# PX4IOv1_3.net
KiCad netlist of a schematic drawn in EAGLE
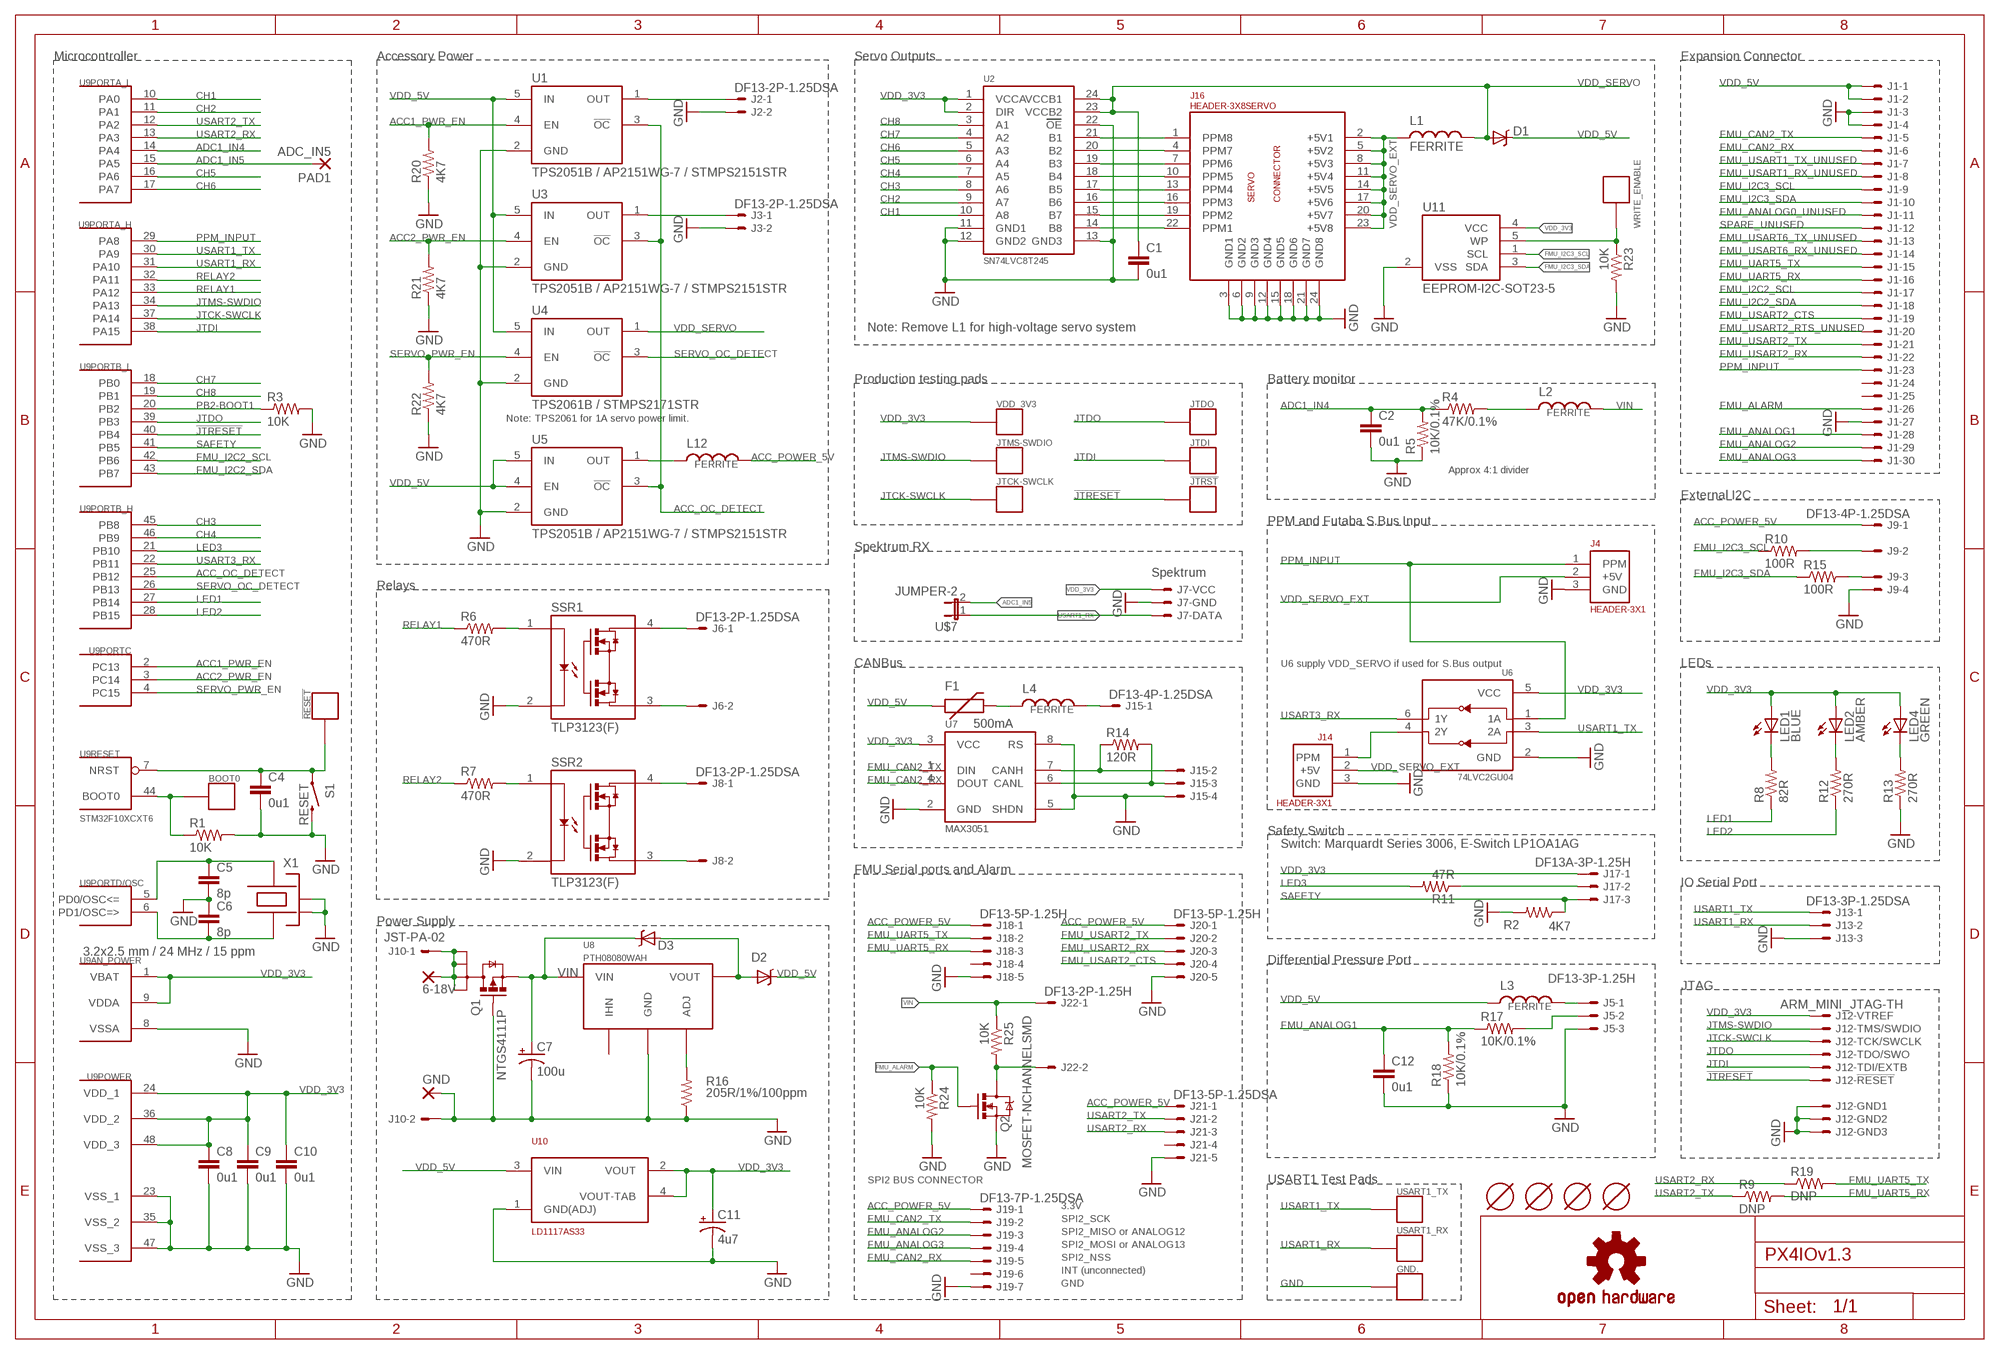
[diagram p0: schematic, sheet 1]

(export (version "E")
  (design (tool "Eeschema 10.0.6"))
  (components
    (comp (ref "!JTRST")
      (value "PAD.04")
      (footprint "eagle-import:PAD.04X.04")
      (libsource (lib "eagle-import") (part "PAD.04"))
    )
    (comp (ref "!RESET")
      (value "PAD.03")
      (footprint "eagle-import:PAD.03X.03")
      (libsource (lib "eagle-import") (part "PAD.03"))
    )
    (comp (ref "6-18V")
      (value "WIREPADSMD3,5-2")
      (footprint "eagle-import:3,5-2")
      (libsource (lib "eagle-import") (part "WIREPADSMD3,5-2"))
    )
    (comp (ref "BOOT0")
      (value "PAD.04")
      (footprint "eagle-import:PAD.04X.04")
      (libsource (lib "eagle-import") (part "PAD.04"))
    )
    (comp (ref "C1")
      (value "0u1")
      (footprint "eagle-import:0402-CAP")
      (fields (field (name "PARTNO") "CC0402ZRY5V7BB104"))
      (libsource (lib "eagle-import") (part "CAP0402-CAP"))
    )
    (comp (ref "C2")
      (value "0u1")
      (footprint "eagle-import:0402-CAP")
      (fields (field (name "PARTNO") "CC0402ZRY5V7BB104"))
      (libsource (lib "eagle-import") (part "CAP0402-CAP"))
    )
    (comp (ref "C4")
      (value "0u1")
      (footprint "eagle-import:0402-CAP")
      (fields (field (name "PARTNO") "CC0402ZRY5V7BB104"))
      (libsource (lib "eagle-import") (part "CAP0402-CAP"))
    )
    (comp (ref "C5")
      (value "8p")
      (footprint "eagle-import:0402-CAP")
      (fields (field (name "PARTNO") "C1005C0G1H080C"))
      (libsource (lib "eagle-import") (part "CAP0402-CAP"))
    )
    (comp (ref "C6")
      (value "8p")
      (footprint "eagle-import:0402-CAP")
      (fields (field (name "PARTNO") "C1005C0G1H080C"))
      (libsource (lib "eagle-import") (part "CAP0402-CAP"))
    )
    (comp (ref "C7")
      (value "100u")
      (footprint "eagle-import:EIA7343")
      (fields (field (name "PARTNO") "T491X107K025ZT"))
      (libsource (lib "eagle-import") (part "CAP_POL7343"))
    )
    (comp (ref "C8")
      (value "0u1")
      (footprint "eagle-import:0402-CAP")
      (fields (field (name "PARTNO") "CC0402ZRY5V7BB104"))
      (libsource (lib "eagle-import") (part "CAP0402-CAP"))
    )
    (comp (ref "C9")
      (value "0u1")
      (footprint "eagle-import:0402-CAP")
      (fields (field (name "PARTNO") "CC0402ZRY5V7BB104"))
      (libsource (lib "eagle-import") (part "CAP0402-CAP"))
    )
    (comp (ref "C10")
      (value "0u1")
      (footprint "eagle-import:0402-CAP")
      (fields (field (name "PARTNO") "CC0402ZRY5V7BB104"))
      (libsource (lib "eagle-import") (part "CAP0402-CAP"))
    )
    (comp (ref "C11")
      (value "4u7")
      (footprint "eagle-import:EIA3216")
      (fields (field (name "PARTNO") "T491A475K010AT"))
      (libsource (lib "eagle-import") (part "CAP_POL1206"))
    )
    (comp (ref "C12")
      (value "0u1")
      (footprint "eagle-import:0402-CAP")
      (fields (field (name "PARTNO") "CC0402ZRY5V7BB104"))
      (libsource (lib "eagle-import") (part "CAP0402-CAP"))
    )
    (comp (ref "D1")
      (value "BAT 60A E6327")
      (footprint "eagle-import:MICROSMP")
      (libsource (lib "eagle-import") (part "DIODE-SCHOTTKY_MSMP"))
    )
    (comp (ref "D2")
      (value "BAT 60A E6327")
      (footprint "eagle-import:MICROSMP")
      (libsource (lib "eagle-import") (part "DIODE-SCHOTTKY_MSMP"))
    )
    (comp (ref "D3")
      (value "MSS1P4-M3/89A")
      (footprint "eagle-import:MICROSMP")
      (libsource (lib "eagle-import") (part "DIODE-SCHOTTKY_MSMP"))
    )
    (comp (ref "F1")
      (value "500mA")
      (footprint "eagle-import:0603")
      (fields (field (name "PARTNO") "MF-FSMF050X-2"))
      (libsource (lib "eagle-import") (part "PTC0603"))
    )
    (comp (ref "GND")
      (value "WIREPADSMD3,5-2")
      (footprint "eagle-import:3,5-2")
      (libsource (lib "eagle-import") (part "WIREPADSMD3,5-2"))
    )
    (comp (ref "GND.")
      (value "PAD.04")
      (footprint "eagle-import:PAD.04X.04")
      (libsource (lib "eagle-import") (part "PAD.04"))
    )
    (comp (ref "J1")
      (value "HEADER_2X15-REV")
      (footprint "eagle-import:HEADER_2MM_2X15_REVERSE")
      (fields (field (name "PARTNO") "951230-2520-AR-PR"))
      (libsource (lib "eagle-import") (part "HEADER_2X15-REV"))
    )
    (comp (ref "J2")
      (value "DF13-2P-1.25DSA")
      (footprint "eagle-import:DF13-2P-1.25DSA")
      (fields (field (name "PARTNO") "DF13-2P-1.25DSA"))
      (libsource (lib "eagle-import") (part "DF13-2P-1.25?DSA"))
    )
    (comp (ref "J3")
      (value "DF13-2P-1.25DSA")
      (footprint "eagle-import:DF13-2P-1.25DSA")
      (fields (field (name "PARTNO") "DF13-2P-1.25DSA"))
      (libsource (lib "eagle-import") (part "DF13-2P-1.25?DSA"))
    )
    (comp (ref "J4")
      (value "HEADER-3X1")
      (footprint "eagle-import:3X1RA")
      (fields (field (name "PARTNO") "53047-02"))
      (libsource (lib "eagle-import") (part "HEADER-3X1RA"))
    )
    (comp (ref "J5")
      (value "DF13-3P-1.25H")
      (footprint "eagle-import:DF13A-3P-1.25H")
      (fields (field (name "PARTNO") "DF13-3P-1.25H(20)"))
      (libsource (lib "eagle-import") (part "DF13-3P-1.25?H"))
    )
    (comp (ref "J6")
      (value "DF13-2P-1.25DSA")
      (footprint "eagle-import:DF13-2P-1.25DSA")
      (fields (field (name "PARTNO") "DF13-2P-1.25DSA"))
      (libsource (lib "eagle-import") (part "DF13-2P-1.25?DSA"))
    )
    (comp (ref "J7")
      (value "CONN_SPEKTRUM_RX-TH")
      (footprint "eagle-import:B3B-ZR")
      (fields (field (name "PARTNO") "B3B-ZR"))
      (libsource (lib "eagle-import") (part "CONN_SPEKTRUM_RX-TH"))
    )
    (comp (ref "J8")
      (value "DF13-2P-1.25DSA")
      (footprint "eagle-import:DF13-2P-1.25DSA")
      (fields (field (name "PARTNO") "DF13-2P-1.25DSA"))
      (libsource (lib "eagle-import") (part "DF13-2P-1.25?DSA"))
    )
    (comp (ref "J9")
      (value "DF13-4P-1.25DSA")
      (footprint "eagle-import:DF13-4P-1.25DSA")
      (fields (field (name "PARTNO") "DF13-4P-1.25DSA"))
      (libsource (lib "eagle-import") (part "DF13-4P-1.25?DSA"))
    )
    (comp (ref "J10")
      (value "JST-PA-02")
      (footprint "eagle-import:S02B-PASK-2")
      (fields (field (name "PARTNO") "S02B-PASK-2"))
      (libsource (lib "eagle-import") (part "JST-PA-02"))
    )
    (comp (ref "J12")
      (value "ARM_MINI_JTAG-TH")
      (footprint "eagle-import:FTSH-105-01-XXX-DV")
      (fields (field (name "PARTNO") "M50-3900542"))
      (libsource (lib "eagle-import") (part "ARM_MINI_JTAG-TH"))
    )
    (comp (ref "J13")
      (value "DF13-3P-1.25DSA")
      (footprint "eagle-import:DF13-3P-1.25DSA")
      (fields (field (name "PARTNO") "DF13-3P-1.25DSA"))
      (libsource (lib "eagle-import") (part "DF13-3P-1.25?DSA"))
    )
    (comp (ref "J14")
      (value "HEADER-3X1")
      (footprint "eagle-import:3X1RA")
      (fields (field (name "PARTNO") "53047-02"))
      (libsource (lib "eagle-import") (part "HEADER-3X1RA"))
    )
    (comp (ref "J15")
      (value "DF13-4P-1.25DSA")
      (footprint "eagle-import:DF13-4P-1.25DSA")
      (fields (field (name "PARTNO") "DF13-4P-1.25DSA"))
      (libsource (lib "eagle-import") (part "DF13-4P-1.25?DSA"))
    )
    (comp (ref "J16")
      (value "HEADER-3X8SERVO")
      (footprint "eagle-import:3X8RA")
      (libsource (lib "eagle-import") (part "HEADER-3X8SERVO"))
    )
    (comp (ref "J17")
      (value "DF13A-3P-1.25H")
      (footprint "eagle-import:DF13A-3P-1.25H")
      (fields (field (name "PARTNO") "DF13A-3P-1.25H(20)"))
      (libsource (lib "eagle-import") (part "DF13-3P-1.25?H"))
    )
    (comp (ref "J18")
      (value "DF13-5P-1.25H")
      (footprint "eagle-import:DF13A-5P-1.25H")
      (fields (field (name "PARTNO") "DF13A-5P-1.25H(20)"))
      (libsource (lib "eagle-import") (part "DF13-5P-1.25?H"))
    )
    (comp (ref "J19")
      (value "DF13-7P-1.25DSA")
      (footprint "eagle-import:DF13-7P-1.25DSA")
      (fields (field (name "PARTNO") "DF13-7P-1.25DSA(20)"))
      (libsource (lib "eagle-import") (part "DF13-7P-1.25?DSA"))
    )
    (comp (ref "J20")
      (value "DF13-5P-1.25H")
      (footprint "eagle-import:DF13A-5P-1.25H")
      (fields (field (name "PARTNO") "DF13A-5P-1.25H(20)"))
      (libsource (lib "eagle-import") (part "DF13-5P-1.25?H"))
    )
    (comp (ref "J21")
      (value "DF13-5P-1.25DSA")
      (footprint "eagle-import:DF13-5P-1.25DSA")
      (fields (field (name "PARTNO") "DF13-5P-1.25DSA(20)"))
      (libsource (lib "eagle-import") (part "DF13-5P-1.25?DSA"))
    )
    (comp (ref "J22")
      (value "DF13-2P-1.25H")
      (footprint "eagle-import:DF13A-2P-1.25H")
      (fields (field (name "PARTNO") "DF13-2P-1.25H(20)"))
      (libsource (lib "eagle-import") (part "DF13-2P-1.25?H"))
    )
    (comp (ref "JTCK-SWCLK")
      (value "PAD.04")
      (footprint "eagle-import:PAD.04X.04")
      (libsource (lib "eagle-import") (part "PAD.04"))
    )
    (comp (ref "JTDI")
      (value "PAD.04")
      (footprint "eagle-import:PAD.04X.04")
      (libsource (lib "eagle-import") (part "PAD.04"))
    )
    (comp (ref "JTDO")
      (value "PAD.04")
      (footprint "eagle-import:PAD.04X.04")
      (libsource (lib "eagle-import") (part "PAD.04"))
    )
    (comp (ref "JTMS-SWDIO")
      (value "PAD.04")
      (footprint "eagle-import:PAD.04X.04")
      (libsource (lib "eagle-import") (part "PAD.04"))
    )
    (comp (ref "L1")
      (value "FERRITE")
      (footprint "eagle-import:0402-IND")
      (fields (field (name "PARTNO") "BKP1005HS121-T"))
      (libsource (lib "eagle-import") (part "INDUCTOR0402"))
    )
    (comp (ref "L2")
      (value "FERRITE")
      (footprint "eagle-import:0402-IND")
      (fields (field (name "PARTNO") "BKP1005HS121-T"))
      (libsource (lib "eagle-import") (part "INDUCTOR0402"))
    )
    (comp (ref "L3")
      (value "FERRITE")
      (footprint "eagle-import:0402-IND")
      (fields (field (name "PARTNO") "BKP1005HS121-T"))
      (libsource (lib "eagle-import") (part "INDUCTOR0402"))
    )
    (comp (ref "L4")
      (value "FERRITE")
      (footprint "eagle-import:0402-IND")
      (fields (field (name "PARTNO") "BKP1005HS121-T"))
      (libsource (lib "eagle-import") (part "INDUCTOR0402"))
    )
    (comp (ref "L12")
      (value "FERRITE")
      (footprint "eagle-import:0402-IND")
      (fields (field (name "PARTNO") "BKP1005HS121-T"))
      (libsource (lib "eagle-import") (part "INDUCTOR0402"))
    )
    (comp (ref "LED1")
      (value "BLUE")
      (footprint "eagle-import:LED-0603")
      (fields (field (name "PARTNO") "LNJ937W8CRA"))
      (libsource (lib "eagle-import") (part "LED0603"))
    )
    (comp (ref "LED2")
      (value "AMBER")
      (footprint "eagle-import:LED-0603")
      (fields (field (name "PARTNO") "LNJ437W84RA"))
      (libsource (lib "eagle-import") (part "LED0603"))
    )
    (comp (ref "LED4")
      (value "GREEN")
      (footprint "eagle-import:LED-0603")
      (fields (field (name "PARTNO") "LNJ337W83RA"))
      (libsource (lib "eagle-import") (part "LED0603"))
    )
    (comp (ref "PAD1")
      (value "ADC_IN5")
      (footprint "eagle-import:PAD-2.5-1.8")
      (libsource (lib "eagle-import") (part "WIREPADSMD2.5-1.8"))
    )
    (comp (ref "Q1")
      (value "NTGS4111P")
      (footprint "eagle-import:TSOP-6")
      (libsource (lib "eagle-import") (part "NTGS4111P"))
    )
    (comp (ref "Q2")
      (value "MOSFET-NCHANNELSMD")
      (footprint "eagle-import:SOT23-3")
      (fields (field (name "PARTNO") "ZXMS6004FFTA"))
      (libsource (lib "eagle-import") (part "MOSFET-NCHANNELSMD"))
    )
    (comp (ref "R1")
      (value "10K")
      (footprint "eagle-import:0402-RES")
      (fields (field (name "PARTNO") "RMCF0402FT10K0"))
      (libsource (lib "eagle-import") (part "RESISTOR0402-RES"))
    )
    (comp (ref "R2")
      (value "4K7")
      (footprint "eagle-import:0402-RES")
      (fields (field (name "PARTNO") "RMCF0402JT4K70"))
      (libsource (lib "eagle-import") (part "RESISTOR0402-RES"))
    )
    (comp (ref "R3")
      (value "10K")
      (footprint "eagle-import:0402-RES")
      (fields (field (name "PARTNO") "RMCF0402FT10K0"))
      (libsource (lib "eagle-import") (part "RESISTOR0402-RES"))
    )
    (comp (ref "R4")
      (value "47K/0.1%")
      (footprint "eagle-import:0402-RES")
      (fields (field (name "PARTNO") "RC0402FR-0747KL"))
      (libsource (lib "eagle-import") (part "RESISTOR0402-RES"))
    )
    (comp (ref "R5")
      (value "10K/0.1%")
      (footprint "eagle-import:0402-RES")
      (fields (field (name "PARTNO") "RMCF0402FT10K0"))
      (libsource (lib "eagle-import") (part "RESISTOR0402-RES"))
    )
    (comp (ref "R6")
      (value "470R")
      (footprint "eagle-import:0402-RES")
      (fields (field (name "PARTNO") "RMCF0402JT470R"))
      (libsource (lib "eagle-import") (part "RESISTOR0402-RES"))
    )
    (comp (ref "R7")
      (value "470R")
      (footprint "eagle-import:0402-RES")
      (fields (field (name "PARTNO") "RMCF0402JT470R"))
      (libsource (lib "eagle-import") (part "RESISTOR0402-RES"))
    )
    (comp (ref "R8")
      (value "82R")
      (footprint "eagle-import:0402-RES")
      (fields (field (name "PARTNO") "MCR01MZPJ820"))
      (libsource (lib "eagle-import") (part "RESISTOR0402-RES"))
    )
    (comp (ref "R9")
      (value "DNP")
      (footprint "eagle-import:0402-RES")
      (fields (field (name "PARTNO") "RMCF0402FT10K0"))
      (libsource (lib "eagle-import") (part "RESISTOR0402-RES"))
    )
    (comp (ref "R10")
      (value "100R")
      (footprint "eagle-import:0402-RES")
      (fields (field (name "PARTNO") "RMCF0402JT100R"))
      (libsource (lib "eagle-import") (part "RESISTOR0402-RES"))
    )
    (comp (ref "R11")
      (value "47R")
      (footprint "eagle-import:0402-RES")
      (fields (field (name "PARTNO") "RMCF0402JT47R0"))
      (libsource (lib "eagle-import") (part "RESISTOR0402-RES"))
    )
    (comp (ref "R12")
      (value "270R")
      (footprint "eagle-import:0402-RES")
      (fields (field (name "PARTNO") "MCR01MZPJ271"))
      (libsource (lib "eagle-import") (part "RESISTOR0402-RES"))
    )
    (comp (ref "R13")
      (value "270R")
      (footprint "eagle-import:0402-RES")
      (fields (field (name "PARTNO") "MCR01MZPJ271"))
      (libsource (lib "eagle-import") (part "RESISTOR0402-RES"))
    )
    (comp (ref "R14")
      (value "120R")
      (footprint "eagle-import:0402-RES")
      (fields (field (name "PARTNO") "P120JCT-ND"))
      (libsource (lib "eagle-import") (part "RESISTOR0402-RES"))
    )
    (comp (ref "R15")
      (value "100R")
      (footprint "eagle-import:0402-RES")
      (fields (field (name "PARTNO") "RMCF0402JT100R"))
      (libsource (lib "eagle-import") (part "RESISTOR0402-RES"))
    )
    (comp (ref "R16")
      (value "205R/1%/100ppm")
      (footprint "eagle-import:0402-RES")
      (fields (field (name "PARTNO") "ERJ-2RKF2050X"))
      (libsource (lib "eagle-import") (part "RESISTOR0402-RES"))
    )
    (comp (ref "R17")
      (value "10K/0.1%")
      (footprint "eagle-import:0402-RES")
      (fields (field (name "PARTNO") "RMCF0402FT10K0"))
      (libsource (lib "eagle-import") (part "RESISTOR0402-RES"))
    )
    (comp (ref "R18")
      (value "10K/0.1%")
      (footprint "eagle-import:0402-RES")
      (fields (field (name "PARTNO") "RMCF0402FT10K0"))
      (libsource (lib "eagle-import") (part "RESISTOR0402-RES"))
    )
    (comp (ref "R19")
      (value "DNP")
      (footprint "eagle-import:0402-RES")
      (fields (field (name "PARTNO") "RMCF0402FT10K0"))
      (libsource (lib "eagle-import") (part "RESISTOR0402-RES"))
    )
    (comp (ref "R20")
      (value "4K7")
      (footprint "eagle-import:0402-RES")
      (fields (field (name "PARTNO") "RMCF0402JT4K70"))
      (libsource (lib "eagle-import") (part "RESISTOR0402-RES"))
    )
    (comp (ref "R21")
      (value "4K7")
      (footprint "eagle-import:0402-RES")
      (fields (field (name "PARTNO") "RMCF0402JT4K70"))
      (libsource (lib "eagle-import") (part "RESISTOR0402-RES"))
    )
    (comp (ref "R22")
      (value "4K7")
      (footprint "eagle-import:0402-RES")
      (fields (field (name "PARTNO") "RMCF0402JT4K70"))
      (libsource (lib "eagle-import") (part "RESISTOR0402-RES"))
    )
    (comp (ref "R23")
      (value "10K")
      (footprint "eagle-import:0402-RES")
      (fields (field (name "PARTNO") "RMCF0402FT10K0"))
      (libsource (lib "eagle-import") (part "RESISTOR0402-RES"))
    )
    (comp (ref "R24")
      (value "10K")
      (footprint "eagle-import:0402-RES")
      (fields (field (name "PARTNO") "RMCF0402FT10K0"))
      (libsource (lib "eagle-import") (part "RESISTOR0402-RES"))
    )
    (comp (ref "R25")
      (value "10K")
      (footprint "eagle-import:0402-RES")
      (fields (field (name "PARTNO") "RMCF0402FT10K0"))
      (libsource (lib "eagle-import") (part "RESISTOR0402-RES"))
    )
    (comp (ref "S1")
      (value "RESET")
      (footprint "eagle-import:EVQP7J01K")
      (fields (field (name "PARTNO") "EVQP7J01K"))
      (libsource (lib "eagle-import") (part "SWITCH-MOMENTARY-2"))
    )
    (comp (ref "SSR1")
      (value "TLP3123(F)")
      (footprint "eagle-import:SOP4-2.54")
      (libsource (lib "eagle-import") (part "TLP3123SO"))
    )
    (comp (ref "SSR2")
      (value "TLP3123(F)")
      (footprint "eagle-import:SOP4-2.54")
      (libsource (lib "eagle-import") (part "TLP3123SO"))
    )
    (comp (ref "U$1")
      (value "OSHW-LOGOS")
      (footprint "eagle-import:OSHW-LOGO-S")
      (libsource (lib "eagle-import") (part "OSHW-LOGOS"))
    )
    (comp (ref "U$2")
      (value "MOUNT-HOLE3.1MM")
      (footprint "eagle-import:MOUNT-HOLE3.1")
      (libsource (lib "eagle-import") (part "MOUNT-HOLE3.1MM"))
    )
    (comp (ref "U$3")
      (value "MOUNT-HOLE3.1MM")
      (footprint "eagle-import:MOUNT-HOLE3.1")
      (libsource (lib "eagle-import") (part "MOUNT-HOLE3.1MM"))
    )
    (comp (ref "U$4")
      (value "MOUNT-HOLE3.1MM")
      (footprint "eagle-import:MOUNT-HOLE3.1")
      (libsource (lib "eagle-import") (part "MOUNT-HOLE3.1MM"))
    )
    (comp (ref "U$5")
      (value "MOUNT-HOLE3.1MM")
      (footprint "eagle-import:MOUNT-HOLE3.1")
      (libsource (lib "eagle-import") (part "MOUNT-HOLE3.1MM"))
    )
    (comp (ref "U$7")
      (value "JUMPER-2")
      (footprint "eagle-import:SJ_2")
      (libsource (lib "eagle-import") (part "JUMPER-2"))
    )
    (comp (ref "U1")
      (value "TPS2051B / AP2151WG-7 / STMPS2151STR")
      (footprint "eagle-import:SOT23-5L")
      (fields (field (name "PARTNO") "AP2151WG-7"))
      (libsource (lib "eagle-import") (part "TPS2051B"))
    )
    (comp (ref "U2")
      (value "SN74LVC8T245")
      (footprint "eagle-import:R-PDSO-G24")
      (fields (field (name "PARTNO") "SN74LVC8T245DBQR"))
      (libsource (lib "eagle-import") (part "SN74LVC8T245"))
    )
    (comp (ref "U3")
      (value "TPS2051B / AP2151WG-7 / STMPS2151STR")
      (footprint "eagle-import:SOT23-5L")
      (fields (field (name "PARTNO") "AP2151WG-7"))
      (libsource (lib "eagle-import") (part "TPS2051B"))
    )
    (comp (ref "U4")
      (value "TPS2061B / STMPS2171STR")
      (footprint "eagle-import:SOT23-5L")
      (fields (field (name "PARTNO") "STMPS2171STR"))
      (libsource (lib "eagle-import") (part "TPS2051B"))
    )
    (comp (ref "U5")
      (value "TPS2051B / AP2151WG-7 / STMPS2151STR")
      (footprint "eagle-import:SOT23-5L")
      (fields (field (name "PARTNO") "AP2151WG-7"))
      (libsource (lib "eagle-import") (part "TPS2051B"))
    )
    (comp (ref "U6")
      (value "74LVC2GU04")
      (footprint "eagle-import:SOT363_PHILIPS")
      (fields (field (name "PARTNO") "74LVC2GU04GW,125"))
      (libsource (lib "eagle-import") (part "74LVC2GU04"))
    )
    (comp (ref "U7")
      (value "MAX3051")
      (footprint "eagle-import:SO08")
      (fields (field (name "PARTNO") "MAX3051ESA+"))
      (libsource (lib "eagle-import") (part "MAX3051"))
    )
    (comp (ref "U8")
      (value "PTH08080WAH")
      (footprint "eagle-import:PTH08080W_TH")
      (libsource (lib "eagle-import") (part "PTH08080WAH"))
    )
    (comp (ref "U9")
      (value "STM32F10XCXT6")
      (footprint "eagle-import:TQFP48")
      (fields (field (name "PARTNO") "STM32F100C8T6B"))
      (libsource (lib "eagle-import") (part "STM32F10XCXT6"))
    )
    (comp (ref "U10")
      (value "LD1117AS33")
      (footprint "eagle-import:SOT-223")
      (libsource (lib "eagle-import") (part "LD1117AS33"))
    )
    (comp (ref "U11")
      (value "EEPROM-I2C-SOT23-5")
      (footprint "eagle-import:SOT23-5")
      (fields (field (name "PARTNO") "24LC01BT-I/OT"))
      (libsource (lib "eagle-import") (part "EEPROM-I2C-?SOT23-5"))
    )
    (comp (ref "USART1_RX")
      (value "PAD.04")
      (footprint "eagle-import:PAD.04X.04")
      (libsource (lib "eagle-import") (part "PAD.04"))
    )
    (comp (ref "USART1_TX")
      (value "PAD.04")
      (footprint "eagle-import:PAD.04X.04")
      (libsource (lib "eagle-import") (part "PAD.04"))
    )
    (comp (ref "VDD_3V3")
      (value "PAD.04")
      (footprint "eagle-import:PAD.04X.04")
      (libsource (lib "eagle-import") (part "PAD.04"))
    )
    (comp (ref "WRITE_ENABLE")
      (value "PAD.04")
      (footprint "eagle-import:PAD.04X.04")
      (libsource (lib "eagle-import") (part "PAD.04"))
    )
    (comp (ref "X1")
      (value "3.2x2.5 mm / 24 MHz / 15 ppm")
      (footprint "eagle-import:OSCILLATOR-3.2X2.5")
      (fields (field (name "PARTNO") "NX3225SA-24.000000MHZ"))
      (libsource (lib "eagle-import") (part "OSCILLATOR-3.2X2.5"))
    )
  )
  (nets
    (net (code "1") (name "/ACC1_PWR_EN") (class "Default")
      (node (ref "R20") (pin "2") (pinfunction "2_2") (pintype "passive"))
      (node (ref "U1") (pin "4") (pinfunction "EN_4") (pintype "input"))
      (node (ref "U9") (pin "2") (pinfunction "PC13_2") (pintype "bidirectional"))
    )
    (net (code "2") (name "/ACC2_PWR_EN") (class "Default")
      (node (ref "R21") (pin "2") (pinfunction "2_2") (pintype "passive"))
      (node (ref "U3") (pin "4") (pinfunction "EN_4") (pintype "input"))
      (node (ref "U9") (pin "3") (pinfunction "PC14_3") (pintype "bidirectional"))
    )
    (net (code "3") (name "/ACC_OC_DETECT") (class "Default")
      (node (ref "U1") (pin "3") (pinfunction "~{OC}_3") (pintype "open_collector"))
      (node (ref "U3") (pin "3") (pinfunction "~{OC}_3") (pintype "open_collector"))
      (node (ref "U5") (pin "3") (pinfunction "~{OC}_3") (pintype "open_collector"))
      (node (ref "U9") (pin "25") (pinfunction "PB12_25") (pintype "bidirectional"))
    )
    (net (code "4") (name "/ACC_POWER_5V") (class "Default")
      (node (ref "J18") (pin "1") (pinfunction "S_1") (pintype "passive"))
      (node (ref "J19") (pin "1") (pinfunction "S_1") (pintype "passive"))
      (node (ref "J20") (pin "1") (pinfunction "S_1") (pintype "passive"))
      (node (ref "J21") (pin "1") (pinfunction "S_1") (pintype "passive"))
      (node (ref "J9") (pin "1") (pinfunction "S_1") (pintype "passive"))
      (node (ref "L12") (pin "2") (pinfunction "2_2") (pintype "passive"))
    )
    (net (code "5") (name "/ADC1_IN4") (class "Default")
      (node (ref "C2") (pin "1") (pinfunction "1_1") (pintype "passive"))
      (node (ref "R4") (pin "1") (pinfunction "1_1") (pintype "passive"))
      (node (ref "R5") (pin "2") (pinfunction "2_2") (pintype "passive"))
      (node (ref "U9") (pin "14") (pinfunction "PA4_14") (pintype "bidirectional"))
    )
    (net (code "6") (name "/CH1") (class "Default")
      (node (ref "U2") (pin "10") (pinfunction "A8_10") (pintype "bidirectional"))
      (node (ref "U9") (pin "10") (pinfunction "PA0_10") (pintype "bidirectional"))
    )
    (net (code "7") (name "/CH2") (class "Default")
      (node (ref "U2") (pin "9") (pinfunction "A7_9") (pintype "bidirectional"))
      (node (ref "U9") (pin "11") (pinfunction "PA1_11") (pintype "bidirectional"))
    )
    (net (code "8") (name "/CH3") (class "Default")
      (node (ref "U2") (pin "8") (pinfunction "A6_8") (pintype "bidirectional"))
      (node (ref "U9") (pin "45") (pinfunction "PB8_45") (pintype "bidirectional"))
    )
    (net (code "9") (name "/CH4") (class "Default")
      (node (ref "U2") (pin "7") (pinfunction "A5_7") (pintype "bidirectional"))
      (node (ref "U9") (pin "46") (pinfunction "PB9_46") (pintype "bidirectional"))
    )
    (net (code "10") (name "/CH5") (class "Default")
      (node (ref "U2") (pin "6") (pinfunction "A4_6") (pintype "bidirectional"))
      (node (ref "U9") (pin "16") (pinfunction "PA6_16") (pintype "bidirectional"))
    )
    (net (code "11") (name "/CH6") (class "Default")
      (node (ref "U2") (pin "5") (pinfunction "A3_5") (pintype "bidirectional"))
      (node (ref "U9") (pin "17") (pinfunction "PA7_17") (pintype "bidirectional"))
    )
    (net (code "12") (name "/CH7") (class "Default")
      (node (ref "U2") (pin "4") (pinfunction "A2_4") (pintype "bidirectional"))
      (node (ref "U9") (pin "18") (pinfunction "PB0_18") (pintype "bidirectional"))
    )
    (net (code "13") (name "/CH8") (class "Default")
      (node (ref "U2") (pin "3") (pinfunction "A1_3") (pintype "bidirectional"))
      (node (ref "U9") (pin "19") (pinfunction "PB1_19") (pintype "bidirectional"))
    )
    (net (code "14") (name "/FMU_ANALOG0_UNUSED") (class "Default")
      (node (ref "J1") (pin "11") (pinfunction "S_11") (pintype "passive"))
    )
    (net (code "15") (name "/FMU_ANALOG1") (class "Default")
      (node (ref "C12") (pin "1") (pinfunction "1_1") (pintype "passive"))
      (node (ref "J1") (pin "28") (pinfunction "S_28") (pintype "passive"))
      (node (ref "R17") (pin "1") (pinfunction "1_1") (pintype "passive"))
      (node (ref "R18") (pin "2") (pinfunction "2_2") (pintype "passive"))
    )
    (net (code "16") (name "/FMU_ANALOG2") (class "Default")
      (node (ref "J1") (pin "29") (pinfunction "S_29") (pintype "passive"))
      (node (ref "J19") (pin "3") (pinfunction "S_3") (pintype "passive"))
    )
    (net (code "17") (name "/FMU_ANALOG3") (class "Default")
      (node (ref "J1") (pin "30") (pinfunction "S_30") (pintype "passive"))
      (node (ref "J19") (pin "4") (pinfunction "S_4") (pintype "passive"))
    )
    (net (code "18") (name "/FMU_CAN2_RX") (class "Default")
      (node (ref "J1") (pin "6") (pinfunction "S_6") (pintype "passive"))
      (node (ref "J19") (pin "5") (pinfunction "S_5") (pintype "passive"))
      (node (ref "U7") (pin "4") (pinfunction "DOUT_4") (pintype "output"))
    )
    (net (code "19") (name "/FMU_CAN2_TX") (class "Default")
      (node (ref "J1") (pin "5") (pinfunction "S_5") (pintype "passive"))
      (node (ref "J19") (pin "2") (pinfunction "S_2") (pintype "passive"))
      (node (ref "U7") (pin "1") (pinfunction "DIN_1") (pintype "input"))
    )
    (net (code "20") (name "/FMU_I2C2_SCL") (class "Default")
      (node (ref "J1") (pin "17") (pinfunction "S_17") (pintype "passive"))
      (node (ref "U9") (pin "42") (pinfunction "PB6_42") (pintype "bidirectional"))
    )
    (net (code "21") (name "/FMU_I2C2_SDA") (class "Default")
      (node (ref "J1") (pin "18") (pinfunction "S_18") (pintype "passive"))
      (node (ref "U9") (pin "43") (pinfunction "PB7_43") (pintype "bidirectional"))
    )
    (net (code "22") (name "/FMU_UART5_RX") (class "Default")
      (node (ref "J1") (pin "16") (pinfunction "S_16") (pintype "passive"))
      (node (ref "J18") (pin "3") (pinfunction "S_3") (pintype "passive"))
      (node (ref "R9") (pin "2") (pinfunction "2_2") (pintype "passive"))
    )
    (net (code "23") (name "/FMU_UART5_TX") (class "Default")
      (node (ref "J1") (pin "15") (pinfunction "S_15") (pintype "passive"))
      (node (ref "J18") (pin "2") (pinfunction "S_2") (pintype "passive"))
      (node (ref "R19") (pin "2") (pinfunction "2_2") (pintype "passive"))
    )
    (net (code "24") (name "/FMU_USART1_RX_UNUSED") (class "Default")
      (node (ref "J1") (pin "8") (pinfunction "S_8") (pintype "passive"))
    )
    (net (code "25") (name "/FMU_USART1_TX_UNUSED") (class "Default")
      (node (ref "J1") (pin "7") (pinfunction "S_7") (pintype "passive"))
    )
    (net (code "26") (name "/FMU_USART2_CTS") (class "Default")
      (node (ref "J1") (pin "19") (pinfunction "S_19") (pintype "passive"))
      (node (ref "J20") (pin "4") (pinfunction "S_4") (pintype "passive"))
    )
    (net (code "27") (name "/FMU_USART2_RTS_UNUSED") (class "Default")
      (node (ref "J1") (pin "20") (pinfunction "S_20") (pintype "passive"))
    )
    (net (code "28") (name "/FMU_USART2_RX") (class "Default")
      (node (ref "J1") (pin "22") (pinfunction "S_22") (pintype "passive"))
      (node (ref "J20") (pin "3") (pinfunction "S_3") (pintype "passive"))
    )
    (net (code "29") (name "/FMU_USART2_TX") (class "Default")
      (node (ref "J1") (pin "21") (pinfunction "S_21") (pintype "passive"))
      (node (ref "J20") (pin "2") (pinfunction "S_2") (pintype "passive"))
    )
    (net (code "30") (name "/FMU_USART6_RX_UNUSED") (class "Default")
      (node (ref "J1") (pin "14") (pinfunction "S_14") (pintype "passive"))
    )
    (net (code "31") (name "/FMU_USART6_TX_UNUSED") (class "Default")
      (node (ref "J1") (pin "13") (pinfunction "S_13") (pintype "passive"))
    )
    (net (code "32") (name "/JTCK-SWCLK") (class "Default")
      (node (ref "J12") (pin "4") (pinfunction "S_4") (pintype "passive"))
      (node (ref "JTCK-SWCLK") (pin "P$1") (pinfunction "P$1_P$1") (pintype "passive"))
      (node (ref "U9") (pin "37") (pinfunction "PA14_37") (pintype "bidirectional"))
    )
    (net (code "33") (name "/JTDI") (class "Default")
      (node (ref "J12") (pin "8") (pinfunction "S_8") (pintype "passive"))
      (node (ref "JTDI") (pin "P$1") (pinfunction "P$1_P$1") (pintype "passive"))
      (node (ref "U9") (pin "38") (pinfunction "PA15_38") (pintype "bidirectional"))
    )
    (net (code "34") (name "/JTDO") (class "Default")
      (node (ref "J12") (pin "6") (pinfunction "S_6") (pintype "passive"))
      (node (ref "JTDO") (pin "P$1") (pinfunction "P$1_P$1") (pintype "passive"))
      (node (ref "U9") (pin "39") (pinfunction "PB3_39") (pintype "bidirectional"))
    )
    (net (code "35") (name "/JTMS-SWDIO") (class "Default")
      (node (ref "J12") (pin "2") (pinfunction "S_2") (pintype "passive"))
      (node (ref "JTMS-SWDIO") (pin "P$1") (pinfunction "P$1_P$1") (pintype "passive"))
      (node (ref "U9") (pin "34") (pinfunction "PA13_34") (pintype "bidirectional"))
    )
    (net (code "36") (name "/LED1") (class "Default")
      (node (ref "R8") (pin "1") (pinfunction "1_1") (pintype "passive"))
      (node (ref "U9") (pin "27") (pinfunction "PB14_27") (pintype "bidirectional"))
    )
    (net (code "37") (name "/LED2") (class "Default")
      (node (ref "R12") (pin "1") (pinfunction "1_1") (pintype "passive"))
      (node (ref "U9") (pin "28") (pinfunction "PB15_28") (pintype "bidirectional"))
    )
    (net (code "38") (name "/LED3") (class "Default")
      (node (ref "R11") (pin "2") (pinfunction "2_2") (pintype "passive"))
      (node (ref "U9") (pin "21") (pinfunction "PB10_21") (pintype "bidirectional"))
    )
    (net (code "39") (name "/PB2-BOOT1") (class "Default")
      (node (ref "R3") (pin "1") (pinfunction "1_1") (pintype "passive"))
      (node (ref "U9") (pin "20") (pinfunction "PB2_20") (pintype "bidirectional"))
    )
    (net (code "40") (name "/PPM_INPUT") (class "Default")
      (node (ref "J1") (pin "23") (pinfunction "S_23") (pintype "passive"))
      (node (ref "J4") (pin "1") (pinfunction "PPM_1") (pintype "bidirectional"))
      (node (ref "U6") (pin "1") (pinfunction "1A_1") (pintype "bidirectional"))
      (node (ref "U9") (pin "29") (pinfunction "PA8_29") (pintype "bidirectional"))
    )
    (net (code "41") (name "/RELAY1") (class "Default")
      (node (ref "R6") (pin "1") (pinfunction "1_1") (pintype "passive"))
      (node (ref "U9") (pin "33") (pinfunction "PA12_33") (pintype "bidirectional"))
    )
    (net (code "42") (name "/RELAY2") (class "Default")
      (node (ref "R7") (pin "1") (pinfunction "1_1") (pintype "passive"))
      (node (ref "U9") (pin "32") (pinfunction "PA11_32") (pintype "bidirectional"))
    )
    (net (code "43") (name "/SAFETY") (class "Default")
      (node (ref "J17") (pin "3") (pinfunction "S_3") (pintype "passive"))
      (node (ref "R2") (pin "1") (pinfunction "1_1") (pintype "passive"))
      (node (ref "U9") (pin "41") (pinfunction "PB5_41") (pintype "bidirectional"))
    )
    (net (code "44") (name "/SERVO_OC_DETECT") (class "Default")
      (node (ref "U4") (pin "3") (pinfunction "~{OC}_3") (pintype "open_collector"))
      (node (ref "U9") (pin "26") (pinfunction "PB13_26") (pintype "bidirectional"))
    )
    (net (code "45") (name "/SERVO_PWR_EN") (class "Default")
      (node (ref "R22") (pin "2") (pinfunction "2_2") (pintype "passive"))
      (node (ref "U4") (pin "4") (pinfunction "EN_4") (pintype "input"))
      (node (ref "U9") (pin "4") (pinfunction "PC15_4") (pintype "bidirectional"))
    )
    (net (code "46") (name "/SPARE_UNUSED") (class "Default")
      (node (ref "J1") (pin "12") (pinfunction "S_12") (pintype "passive"))
    )
    (net (code "47") (name "/USART1_TX") (class "Default")
      (node (ref "J13") (pin "1") (pinfunction "S_1") (pintype "passive"))
      (node (ref "U6") (pin "3") (pinfunction "2A_3") (pintype "bidirectional"))
      (node (ref "U9") (pin "30") (pinfunction "PA9_30") (pintype "bidirectional"))
      (node (ref "USART1_TX") (pin "P$1") (pinfunction "P$1_P$1") (pintype "passive"))
    )
    (net (code "48") (name "/USART2_RX") (class "Default")
      (node (ref "J21") (pin "3") (pinfunction "S_3") (pintype "passive"))
      (node (ref "R19") (pin "1") (pinfunction "1_1") (pintype "passive"))
      (node (ref "U9") (pin "13") (pinfunction "PA3_13") (pintype "bidirectional"))
    )
    (net (code "49") (name "/USART2_TX") (class "Default")
      (node (ref "J21") (pin "2") (pinfunction "S_2") (pintype "passive"))
      (node (ref "R9") (pin "1") (pinfunction "1_1") (pintype "passive"))
      (node (ref "U9") (pin "12") (pinfunction "PA2_12") (pintype "bidirectional"))
    )
    (net (code "50") (name "/USART3_RX") (class "Default")
      (node (ref "U6") (pin "6") (pinfunction "1Y_6") (pintype "bidirectional"))
      (node (ref "U9") (pin "22") (pinfunction "PB11_22") (pintype "bidirectional"))
    )
    (net (code "51") (name "/VDD_5V") (class "Default")
      (node (ref "D1") (pin "CATHODE") (pinfunction "C_CATHODE") (pintype "passive"))
      (node (ref "D2") (pin "CATHODE") (pinfunction "C_CATHODE") (pintype "passive"))
      (node (ref "F1") (pin "1") (pinfunction "1_1") (pintype "bidirectional"))
      (node (ref "J1") (pin "1") (pinfunction "S_1") (pintype "passive"))
      (node (ref "J1") (pin "2") (pinfunction "S_2") (pintype "passive"))
      (node (ref "L3") (pin "1") (pinfunction "1_1") (pintype "passive"))
      (node (ref "U1") (pin "5") (pinfunction "IN_5") (pintype "power_in"))
      (node (ref "U10") (pin "3") (pinfunction "VIN_3") (pintype "bidirectional"))
      (node (ref "U3") (pin "5") (pinfunction "IN_5") (pintype "power_in"))
      (node (ref "U4") (pin "5") (pinfunction "IN_5") (pintype "power_in"))
      (node (ref "U5") (pin "4") (pinfunction "EN_4") (pintype "input"))
      (node (ref "U5") (pin "5") (pinfunction "IN_5") (pintype "power_in"))
    )
    (net (code "52") (name "/VDD_SERVO") (class "Default")
      (node (ref "C1") (pin "1") (pinfunction "1_1") (pintype "passive"))
      (node (ref "D1") (pin "ANODE") (pinfunction "A_ANODE") (pintype "passive"))
      (node (ref "L1") (pin "2") (pinfunction "2_2") (pintype "passive"))
      (node (ref "U2") (pin "23") (pinfunction "VCCB2_23") (pintype "bidirectional"))
      (node (ref "U2") (pin "24") (pinfunction "VCCB1_24") (pintype "bidirectional"))
      (node (ref "U4") (pin "1") (pinfunction "OUT_1") (pintype "output"))
    )
    (net (code "53") (name "/VDD_SERVO_EXT") (class "Default")
      (node (ref "J14") (pin "2") (pinfunction "+5V_2") (pintype "bidirectional"))
      (node (ref "J16") (pin "11") (pinfunction "+5V4_11") (pintype "bidirectional"))
      (node (ref "J16") (pin "14") (pinfunction "+5V5_14") (pintype "bidirectional"))
      (node (ref "J16") (pin "17") (pinfunction "+5V6_17") (pintype "bidirectional"))
      (node (ref "J16") (pin "2") (pinfunction "+5V1_2") (pintype "bidirectional"))
      (node (ref "J16") (pin "20") (pinfunction "+5V7_20") (pintype "bidirectional"))
      (node (ref "J16") (pin "23") (pinfunction "+5V8_23") (pintype "bidirectional"))
      (node (ref "J16") (pin "5") (pinfunction "+5V2_5") (pintype "bidirectional"))
      (node (ref "J16") (pin "8") (pinfunction "+5V3_8") (pintype "bidirectional"))
      (node (ref "J4") (pin "2") (pinfunction "+5V_2") (pintype "bidirectional"))
      (node (ref "L1") (pin "1") (pinfunction "1_1") (pintype "passive"))
    )
    (net (code "54") (name "/~{JTRESET}") (class "Default")
      (node (ref "!JTRST") (pin "P$1") (pinfunction "P$1_P$1") (pintype "passive"))
      (node (ref "J12") (pin "10") (pinfunction "S_10") (pintype "passive"))
      (node (ref "U9") (pin "40") (pinfunction "PB4_40") (pintype "bidirectional"))
    )
    (net (code "55") (name "ADC1_IN5") (class "Default")
      (node (ref "PAD1") (pin "P$1") (pinfunction "P_P$1") (pintype "passive"))
      (node (ref "U$7") (pin "2") (pinfunction "2_2") (pintype "passive"))
      (node (ref "U9") (pin "15") (pinfunction "PA5_15") (pintype "bidirectional"))
    )
    (net (code "56") (name "FMU_ALARM") (class "Default")
      (node (ref "J1") (pin "26") (pinfunction "S_26") (pintype "passive"))
      (node (ref "Q2") (pin "1") (pinfunction "G_1") (pintype "passive"))
      (node (ref "R24") (pin "1") (pinfunction "1_1") (pintype "passive"))
    )
    (net (code "57") (name "FMU_I2C3_SCL") (class "Default")
      (node (ref "J1") (pin "9") (pinfunction "S_9") (pintype "passive"))
      (node (ref "R10") (pin "1") (pinfunction "1_1") (pintype "passive"))
      (node (ref "U11") (pin "1") (pinfunction "SCL_1") (pintype "bidirectional"))
    )
    (net (code "58") (name "FMU_I2C3_SDA") (class "Default")
      (node (ref "J1") (pin "10") (pinfunction "S_10") (pintype "passive"))
      (node (ref "R15") (pin "1") (pinfunction "1_1") (pintype "passive"))
      (node (ref "U11") (pin "3") (pinfunction "SDA_3") (pintype "bidirectional"))
    )
    (net (code "59") (name "GND") (class "Default")
      (node (ref "C1") (pin "2") (pinfunction "2_2") (pintype "passive"))
      (node (ref "C10") (pin "2") (pinfunction "2_2") (pintype "passive"))
      (node (ref "C11") (pin "C") (pinfunction "-_C") (pintype "passive"))
      (node (ref "C12") (pin "2") (pinfunction "2_2") (pintype "passive"))
      (node (ref "C2") (pin "2") (pinfunction "2_2") (pintype "passive"))
      (node (ref "C4") (pin "2") (pinfunction "2_2") (pintype "passive"))
      (node (ref "C5") (pin "2") (pinfunction "2_2") (pintype "passive"))
      (node (ref "C6") (pin "1") (pinfunction "1_1") (pintype "passive"))
      (node (ref "C7") (pin "C") (pinfunction "-_C") (pintype "passive"))
      (node (ref "C8") (pin "2") (pinfunction "2_2") (pintype "passive"))
      (node (ref "C9") (pin "2") (pinfunction "2_2") (pintype "passive"))
      (node (ref "GND") (pin "1") (pinfunction "P_1") (pintype "passive"))
      (node (ref "GND.") (pin "P$1") (pinfunction "P$1_P$1") (pintype "passive"))
      (node (ref "J1") (pin "27") (pinfunction "S_27") (pintype "passive"))
      (node (ref "J1") (pin "3") (pinfunction "S_3") (pintype "passive"))
      (node (ref "J1") (pin "4") (pinfunction "S_4") (pintype "passive"))
      (node (ref "J10") (pin "2") (pinfunction "S_2") (pintype "passive"))
      (node (ref "J12") (pin "3") (pinfunction "S_3") (pintype "passive"))
      (node (ref "J12") (pin "5") (pinfunction "S_5") (pintype "passive"))
      (node (ref "J12") (pin "9") (pinfunction "S_9") (pintype "passive"))
      (node (ref "J13") (pin "3") (pinfunction "S_3") (pintype "passive"))
      (node (ref "J14") (pin "3") (pinfunction "GND_3") (pintype "bidirectional"))
      (node (ref "J15") (pin "4") (pinfunction "S_4") (pintype "passive"))
      (node (ref "J16") (pin "12") (pinfunction "GND4_12") (pintype "bidirectional"))
      (node (ref "J16") (pin "15") (pinfunction "GND5_15") (pintype "bidirectional"))
      (node (ref "J16") (pin "18") (pinfunction "GND6_18") (pintype "bidirectional"))
      (node (ref "J16") (pin "21") (pinfunction "GND7_21") (pintype "bidirectional"))
      (node (ref "J16") (pin "24") (pinfunction "GND8_24") (pintype "bidirectional"))
      (node (ref "J16") (pin "3") (pinfunction "GND1_3") (pintype "bidirectional"))
      (node (ref "J16") (pin "6") (pinfunction "GND2_6") (pintype "bidirectional"))
      (node (ref "J16") (pin "9") (pinfunction "GND3_9") (pintype "bidirectional"))
      (node (ref "J18") (pin "5") (pinfunction "S_5") (pintype "passive"))
      (node (ref "J19") (pin "7") (pinfunction "S_7") (pintype "passive"))
      (node (ref "J2") (pin "2") (pinfunction "S_2") (pintype "passive"))
      (node (ref "J20") (pin "5") (pinfunction "S_5") (pintype "passive"))
      (node (ref "J21") (pin "5") (pinfunction "S_5") (pintype "passive"))
      (node (ref "J3") (pin "2") (pinfunction "S_2") (pintype "passive"))
      (node (ref "J4") (pin "3") (pinfunction "GND_3") (pintype "bidirectional"))
      (node (ref "J5") (pin "3") (pinfunction "S_3") (pintype "passive"))
      (node (ref "J7") (pin "2") (pinfunction "S_2") (pintype "passive"))
      (node (ref "J9") (pin "4") (pinfunction "S_4") (pintype "passive"))
      (node (ref "Q1") (pin "3") (pinfunction "G_3") (pintype "passive"))
      (node (ref "Q2") (pin "2") (pinfunction "S_2") (pintype "passive"))
      (node (ref "R1") (pin "2") (pinfunction "2_2") (pintype "passive"))
      (node (ref "R13") (pin "1") (pinfunction "1_1") (pintype "passive"))
      (node (ref "R16") (pin "1") (pinfunction "1_1") (pintype "passive"))
      (node (ref "R18") (pin "1") (pinfunction "1_1") (pintype "passive"))
      (node (ref "R2") (pin "2") (pinfunction "2_2") (pintype "passive"))
      (node (ref "R20") (pin "1") (pinfunction "1_1") (pintype "passive"))
      (node (ref "R21") (pin "1") (pinfunction "1_1") (pintype "passive"))
      (node (ref "R22") (pin "1") (pinfunction "1_1") (pintype "passive"))
      (node (ref "R23") (pin "2") (pinfunction "2_2") (pintype "passive"))
      (node (ref "R24") (pin "2") (pinfunction "2_2") (pintype "passive"))
      (node (ref "R3") (pin "2") (pinfunction "2_2") (pintype "passive"))
      (node (ref "R5") (pin "1") (pinfunction "1_1") (pintype "passive"))
      (node (ref "S1") (pin "B3") (pinfunction "2_B3") (pintype "passive"))
      (node (ref "SSR1") (pin "2") (pinfunction "2_2") (pintype "bidirectional"))
      (node (ref "SSR2") (pin "2") (pinfunction "2_2") (pintype "bidirectional"))
      (node (ref "U1") (pin "2") (pinfunction "GND_2") (pintype "power_in"))
      (node (ref "U10") (pin "1") (pinfunction "GND(ADJ)_1") (pintype "bidirectional"))
      (node (ref "U11") (pin "2") (pinfunction "VSS_2") (pintype "power_in"))
      (node (ref "U2") (pin "11") (pinfunction "GND1_11") (pintype "bidirectional"))
      (node (ref "U2") (pin "12") (pinfunction "GND2_12") (pintype "bidirectional"))
      (node (ref "U2") (pin "13") (pinfunction "GND3_13") (pintype "bidirectional"))
      (node (ref "U2") (pin "22") (pinfunction "OE_22") (pintype "bidirectional"))
      (node (ref "U3") (pin "2") (pinfunction "GND_2") (pintype "power_in"))
      (node (ref "U4") (pin "2") (pinfunction "GND_2") (pintype "power_in"))
      (node (ref "U5") (pin "2") (pinfunction "GND_2") (pintype "power_in"))
      (node (ref "U6") (pin "2") (pinfunction "GND_2") (pintype "power_in"))
      (node (ref "U7") (pin "2") (pinfunction "GND_2") (pintype "power_in"))
      (node (ref "U7") (pin "5") (pinfunction "SHDN_5") (pintype "input"))
      (node (ref "U7") (pin "8") (pinfunction "RS_8") (pintype "input"))
      (node (ref "U8") (pin "2") (pinfunction "GND_2") (pintype "power_in"))
      (node (ref "U9") (pin "23") (pinfunction "VSS_1_23") (pintype "power_in"))
      (node (ref "U9") (pin "35") (pinfunction "VSS_2_35") (pintype "power_in"))
      (node (ref "U9") (pin "47") (pinfunction "VSS_3_47") (pintype "power_in"))
      (node (ref "U9") (pin "8") (pinfunction "VSSA_8") (pintype "power_in"))
      (node (ref "X1") (pin "2") (pinfunction "NC_2_2") (pintype "power_in"))
      (node (ref "X1") (pin "4") (pinfunction "NC_4_4") (pintype "power_in"))
    )
    (net (code "60") (name "Net-(6-18V-P)") (class "Default")
      (node (ref "6-18V") (pin "1") (pinfunction "P_1") (pintype "passive"))
      (node (ref "J10") (pin "1") (pinfunction "S_1") (pintype "passive"))
      (node (ref "Q1") (pin "1") (pinfunction "D_1") (pintype "passive"))
      (node (ref "Q1") (pin "2") (pinfunction "D1_2") (pintype "passive"))
      (node (ref "Q1") (pin "5") (pinfunction "D2_5") (pintype "passive"))
      (node (ref "Q1") (pin "6") (pinfunction "D3_6") (pintype "passive"))
    )
    (net (code "61") (name "Net-(D2-A)") (class "Default")
      (node (ref "D2") (pin "ANODE") (pinfunction "A_ANODE") (pintype "passive"))
      (node (ref "D3") (pin "ANODE") (pinfunction "A_ANODE") (pintype "passive"))
      (node (ref "U8") (pin "3") (pinfunction "VOUT_3") (pintype "power_in"))
    )
    (net (code "62") (name "Net-(F1-Pad2)") (class "Default")
      (node (ref "F1") (pin "2") (pinfunction "2_2") (pintype "bidirectional"))
      (node (ref "L4") (pin "1") (pinfunction "1_1") (pintype "passive"))
    )
    (net (code "63") (name "Net-(J2A-S)") (class "Default")
      (node (ref "J2") (pin "1") (pinfunction "S_1") (pintype "passive"))
      (node (ref "U1") (pin "1") (pinfunction "OUT_1") (pintype "output"))
    )
    (net (code "64") (name "Net-(J3A-S)") (class "Default")
      (node (ref "J3") (pin "1") (pinfunction "S_1") (pintype "passive"))
      (node (ref "U3") (pin "1") (pinfunction "OUT_1") (pintype "output"))
    )
    (net (code "65") (name "Net-(J5A-S)") (class "Default")
      (node (ref "J5") (pin "1") (pinfunction "S_1") (pintype "passive"))
      (node (ref "L3") (pin "2") (pinfunction "2_2") (pintype "passive"))
    )
    (net (code "66") (name "Net-(J5B-S)") (class "Default")
      (node (ref "J5") (pin "2") (pinfunction "S_2") (pintype "passive"))
      (node (ref "R17") (pin "2") (pinfunction "2_2") (pintype "passive"))
    )
    (net (code "67") (name "Net-(J6A-S)") (class "Default")
      (node (ref "J6") (pin "1") (pinfunction "S_1") (pintype "passive"))
      (node (ref "SSR1") (pin "4") (pinfunction "4_4") (pintype "bidirectional"))
    )
    (net (code "68") (name "Net-(J6B-S)") (class "Default")
      (node (ref "J6") (pin "2") (pinfunction "S_2") (pintype "passive"))
      (node (ref "SSR1") (pin "3") (pinfunction "3_3") (pintype "bidirectional"))
    )
    (net (code "69") (name "Net-(J8A-S)") (class "Default")
      (node (ref "J8") (pin "1") (pinfunction "S_1") (pintype "passive"))
      (node (ref "SSR2") (pin "4") (pinfunction "4_4") (pintype "bidirectional"))
    )
    (net (code "70") (name "Net-(J8B-S)") (class "Default")
      (node (ref "J8") (pin "2") (pinfunction "S_2") (pintype "passive"))
      (node (ref "SSR2") (pin "3") (pinfunction "3_3") (pintype "bidirectional"))
    )
    (net (code "71") (name "Net-(J9B-S)") (class "Default")
      (node (ref "J9") (pin "2") (pinfunction "S_2") (pintype "passive"))
      (node (ref "R10") (pin "2") (pinfunction "2_2") (pintype "passive"))
    )
    (net (code "72") (name "Net-(J9C-S)") (class "Default")
      (node (ref "J9") (pin "3") (pinfunction "S_3") (pintype "passive"))
      (node (ref "R15") (pin "2") (pinfunction "2_2") (pintype "passive"))
    )
    (net (code "73") (name "Net-(J14-PPM)") (class "Default")
      (node (ref "J14") (pin "1") (pinfunction "PPM_1") (pintype "bidirectional"))
      (node (ref "U6") (pin "4") (pinfunction "2Y_4") (pintype "bidirectional"))
    )
    (net (code "74") (name "Net-(J15A-S)") (class "Default")
      (node (ref "J15") (pin "1") (pinfunction "S_1") (pintype "passive"))
      (node (ref "L4") (pin "2") (pinfunction "2_2") (pintype "passive"))
    )
    (net (code "75") (name "Net-(J15B-S)") (class "Default")
      (node (ref "J15") (pin "2") (pinfunction "S_2") (pintype "passive"))
      (node (ref "R14") (pin "1") (pinfunction "1_1") (pintype "passive"))
      (node (ref "U7") (pin "7") (pinfunction "CANH_7") (pintype "bidirectional"))
    )
    (net (code "76") (name "Net-(J15C-S)") (class "Default")
      (node (ref "J15") (pin "3") (pinfunction "S_3") (pintype "passive"))
      (node (ref "R14") (pin "2") (pinfunction "2_2") (pintype "passive"))
      (node (ref "U7") (pin "6") (pinfunction "CANL_6") (pintype "bidirectional"))
    )
    (net (code "77") (name "Net-(J16-PPM1)") (class "Default")
      (node (ref "J16") (pin "22") (pinfunction "PPM1_22") (pintype "bidirectional"))
      (node (ref "U2") (pin "14") (pinfunction "B8_14") (pintype "bidirectional"))
    )
    (net (code "78") (name "Net-(J16-PPM2)") (class "Default")
      (node (ref "J16") (pin "19") (pinfunction "PPM2_19") (pintype "bidirectional"))
      (node (ref "U2") (pin "15") (pinfunction "B7_15") (pintype "bidirectional"))
    )
    (net (code "79") (name "Net-(J16-PPM3)") (class "Default")
      (node (ref "J16") (pin "16") (pinfunction "PPM3_16") (pintype "bidirectional"))
      (node (ref "U2") (pin "16") (pinfunction "B6_16") (pintype "bidirectional"))
    )
    (net (code "80") (name "Net-(J16-PPM4)") (class "Default")
      (node (ref "J16") (pin "13") (pinfunction "PPM4_13") (pintype "bidirectional"))
      (node (ref "U2") (pin "17") (pinfunction "B5_17") (pintype "bidirectional"))
    )
    (net (code "81") (name "Net-(J16-PPM5)") (class "Default")
      (node (ref "J16") (pin "10") (pinfunction "PPM5_10") (pintype "bidirectional"))
      (node (ref "U2") (pin "18") (pinfunction "B4_18") (pintype "bidirectional"))
    )
    (net (code "82") (name "Net-(J16-PPM6)") (class "Default")
      (node (ref "J16") (pin "7") (pinfunction "PPM6_7") (pintype "bidirectional"))
      (node (ref "U2") (pin "19") (pinfunction "B3_19") (pintype "bidirectional"))
    )
    (net (code "83") (name "Net-(J16-PPM7)") (class "Default")
      (node (ref "J16") (pin "4") (pinfunction "PPM7_4") (pintype "bidirectional"))
      (node (ref "U2") (pin "20") (pinfunction "B2_20") (pintype "bidirectional"))
    )
    (net (code "84") (name "Net-(J16-PPM8)") (class "Default")
      (node (ref "J16") (pin "1") (pinfunction "PPM8_1") (pintype "bidirectional"))
      (node (ref "U2") (pin "21") (pinfunction "B1_21") (pintype "bidirectional"))
    )
    (net (code "85") (name "Net-(J17B-S)") (class "Default")
      (node (ref "J17") (pin "2") (pinfunction "S_2") (pintype "passive"))
      (node (ref "R11") (pin "1") (pinfunction "1_1") (pintype "passive"))
    )
    (net (code "86") (name "Net-(J22B-S)") (class "Default")
      (node (ref "J22") (pin "2") (pinfunction "S_2") (pintype "passive"))
      (node (ref "Q2") (pin "3") (pinfunction "D_3") (pintype "passive"))
      (node (ref "R25") (pin "2") (pinfunction "2_2") (pintype "passive"))
    )
    (net (code "87") (name "Net-(L2-Pad1)") (class "Default")
      (node (ref "L2") (pin "1") (pinfunction "1_1") (pintype "passive"))
      (node (ref "R4") (pin "2") (pinfunction "2_2") (pintype "passive"))
    )
    (net (code "88") (name "Net-(LED1-PadC)") (class "Default")
      (node (ref "LED1") (pin "C") (pinfunction "C_C") (pintype "passive"))
      (node (ref "R8") (pin "2") (pinfunction "2_2") (pintype "passive"))
    )
    (net (code "89") (name "Net-(LED2-PadC)") (class "Default")
      (node (ref "LED2") (pin "C") (pinfunction "C_C") (pintype "passive"))
      (node (ref "R12") (pin "2") (pinfunction "2_2") (pintype "passive"))
    )
    (net (code "90") (name "Net-(LED4-PadC)") (class "Default")
      (node (ref "LED4") (pin "C") (pinfunction "C_C") (pintype "passive"))
      (node (ref "R13") (pin "2") (pinfunction "2_2") (pintype "passive"))
    )
    (net (code "91") (name "Net-(R6-Pad2)") (class "Default")
      (node (ref "R6") (pin "2") (pinfunction "2_2") (pintype "passive"))
      (node (ref "SSR1") (pin "1") (pinfunction "1_1") (pintype "bidirectional"))
    )
    (net (code "92") (name "Net-(R7-Pad2)") (class "Default")
      (node (ref "R7") (pin "2") (pinfunction "2_2") (pintype "passive"))
      (node (ref "SSR2") (pin "1") (pinfunction "1_1") (pintype "bidirectional"))
    )
    (net (code "93") (name "Net-(S1-1)") (class "Default")
      (node (ref "!RESET") (pin "P$1") (pinfunction "P$1_P$1") (pintype "passive"))
      (node (ref "C4") (pin "1") (pinfunction "1_1") (pintype "passive"))
      (node (ref "S1") (pin "A1") (pinfunction "1_A1") (pintype "passive"))
      (node (ref "U9") (pin "7") (pinfunction "NRST_7") (pintype "input"))
    )
    (net (code "94") (name "Net-(U5-OUT)") (class "Default")
      (node (ref "L12") (pin "1") (pinfunction "1_1") (pintype "passive"))
      (node (ref "U5") (pin "1") (pinfunction "OUT_1") (pintype "output"))
    )
    (net (code "95") (name "Net-(U8-ADJ)") (class "Default")
      (node (ref "R16") (pin "2") (pinfunction "2_2") (pintype "passive"))
      (node (ref "U8") (pin "4") (pinfunction "ADJ_4") (pintype "bidirectional"))
    )
    (net (code "96") (name "Net-(U9G-PD0{slash}OSC<=)") (class "Default")
      (node (ref "C5") (pin "1") (pinfunction "1_1") (pintype "passive"))
      (node (ref "U9") (pin "5") (pinfunction "PD0/OSC<=_5") (pintype "bidirectional"))
      (node (ref "X1") (pin "3") (pinfunction "3_3") (pintype "bidirectional"))
    )
    (net (code "97") (name "Net-(U9G-PD1{slash}OSC=>)") (class "Default")
      (node (ref "C6") (pin "2") (pinfunction "2_2") (pintype "passive"))
      (node (ref "U9") (pin "6") (pinfunction "PD1/OSC=>_6") (pintype "bidirectional"))
      (node (ref "X1") (pin "1") (pinfunction "1_1") (pintype "bidirectional"))
    )
    (net (code "98") (name "Net-(U9I-BOOT0)") (class "Default")
      (node (ref "BOOT0") (pin "P$1") (pinfunction "P$1_P$1") (pintype "passive"))
      (node (ref "R1") (pin "1") (pinfunction "1_1") (pintype "passive"))
      (node (ref "U9") (pin "44") (pinfunction "BOOT0_44") (pintype "input"))
    )
    (net (code "99") (name "Net-(U11-WP)") (class "Default")
      (node (ref "R23") (pin "1") (pinfunction "1_1") (pintype "passive"))
      (node (ref "U11") (pin "5") (pinfunction "WP_5") (pintype "bidirectional"))
      (node (ref "WRITE_ENABLE") (pin "P$1") (pinfunction "P$1_P$1") (pintype "passive"))
    )
    (net (code "100") (name "USART1_RX") (class "Default")
      (node (ref "J13") (pin "2") (pinfunction "S_2") (pintype "passive"))
      (node (ref "J7") (pin "1") (pinfunction "S_1") (pintype "passive"))
      (node (ref "U$7") (pin "1") (pinfunction "1_1") (pintype "passive"))
      (node (ref "U9") (pin "31") (pinfunction "PA10_31") (pintype "bidirectional"))
      (node (ref "USART1_RX") (pin "P$1") (pinfunction "P$1_P$1") (pintype "passive"))
    )
    (net (code "101") (name "VDD_3V3") (class "Default")
      (node (ref "C10") (pin "1") (pinfunction "1_1") (pintype "passive"))
      (node (ref "C11") (pin "A") (pinfunction "+_A") (pintype "passive"))
      (node (ref "C8") (pin "1") (pinfunction "1_1") (pintype "passive"))
      (node (ref "C9") (pin "1") (pinfunction "1_1") (pintype "passive"))
      (node (ref "J12") (pin "1") (pinfunction "S_1") (pintype "passive"))
      (node (ref "J17") (pin "1") (pinfunction "S_1") (pintype "passive"))
      (node (ref "J7") (pin "3") (pinfunction "S_3") (pintype "passive"))
      (node (ref "LED1") (pin "A") (pinfunction "A_A") (pintype "passive"))
      (node (ref "LED2") (pin "A") (pinfunction "A_A") (pintype "passive"))
      (node (ref "LED4") (pin "A") (pinfunction "A_A") (pintype "passive"))
      (node (ref "U10") (pin "2") (pinfunction "VOUT_2") (pintype "bidirectional"))
      (node (ref "U10") (pin "4") (pinfunction "VOUT-TAB_4") (pintype "bidirectional"))
      (node (ref "U11") (pin "4") (pinfunction "VCC_4") (pintype "power_in"))
      (node (ref "U2") (pin "1") (pinfunction "VCCA_1") (pintype "bidirectional"))
      (node (ref "U2") (pin "2") (pinfunction "DIR_2") (pintype "bidirectional"))
      (node (ref "U6") (pin "5") (pinfunction "VCC_5") (pintype "power_in"))
      (node (ref "U7") (pin "3") (pinfunction "VCC_3") (pintype "input"))
      (node (ref "U9") (pin "1") (pinfunction "VBAT_1") (pintype "power_in"))
      (node (ref "U9") (pin "24") (pinfunction "VDD_1_24") (pintype "power_in"))
      (node (ref "U9") (pin "36") (pinfunction "VDD_2_36") (pintype "power_in"))
      (node (ref "U9") (pin "48") (pinfunction "VDD_3_48") (pintype "power_in"))
      (node (ref "U9") (pin "9") (pinfunction "VDDA_9") (pintype "power_in"))
      (node (ref "VDD_3V3") (pin "P$1") (pinfunction "P$1_P$1") (pintype "passive"))
    )
    (net (code "102") (name "VIN") (class "Default")
      (node (ref "C7") (pin "A") (pinfunction "+_A") (pintype "passive"))
      (node (ref "D3") (pin "CATHODE") (pinfunction "C_CATHODE") (pintype "passive"))
      (node (ref "J22") (pin "1") (pinfunction "S_1") (pintype "passive"))
      (node (ref "L2") (pin "2") (pinfunction "2_2") (pintype "passive"))
      (node (ref "Q1") (pin "4") (pinfunction "S_4") (pintype "passive"))
      (node (ref "R25") (pin "1") (pinfunction "1_1") (pintype "passive"))
      (node (ref "U8") (pin "1") (pinfunction "VIN_1") (pintype "power_in"))
    )
    (net (code "103") (name "unconnected-(J1Q-S-Pad24)") (class "Default")
      (node (ref "J1") (pin "24") (pinfunction "S_24") (pintype "passive"))
    )
    (net (code "104") (name "unconnected-(J1R-S-Pad25)") (class "Default")
      (node (ref "J1") (pin "25") (pinfunction "S_25") (pintype "passive"))
    )
    (net (code "105") (name "unconnected-(J18D-S-Pad4)") (class "Default")
      (node (ref "J18") (pin "4") (pinfunction "S_4") (pintype "passive"))
    )
    (net (code "106") (name "unconnected-(J19F-S-Pad6)") (class "Default")
      (node (ref "J19") (pin "6") (pinfunction "S_6") (pintype "passive"))
    )
    (net (code "107") (name "unconnected-(J21D-S-Pad4)") (class "Default")
      (node (ref "J21") (pin "4") (pinfunction "S_4") (pintype "passive"))
    )
    (net (code "108") (name "unconnected-(U8-IHN-Pad5)") (class "Default")
      (node (ref "U8") (pin "5") (pinfunction "IHN_5") (pintype "bidirectional"))
    )
  )
)
